# 04_4G.net
KiCad netlist of a schematic drawn in Altium Designer
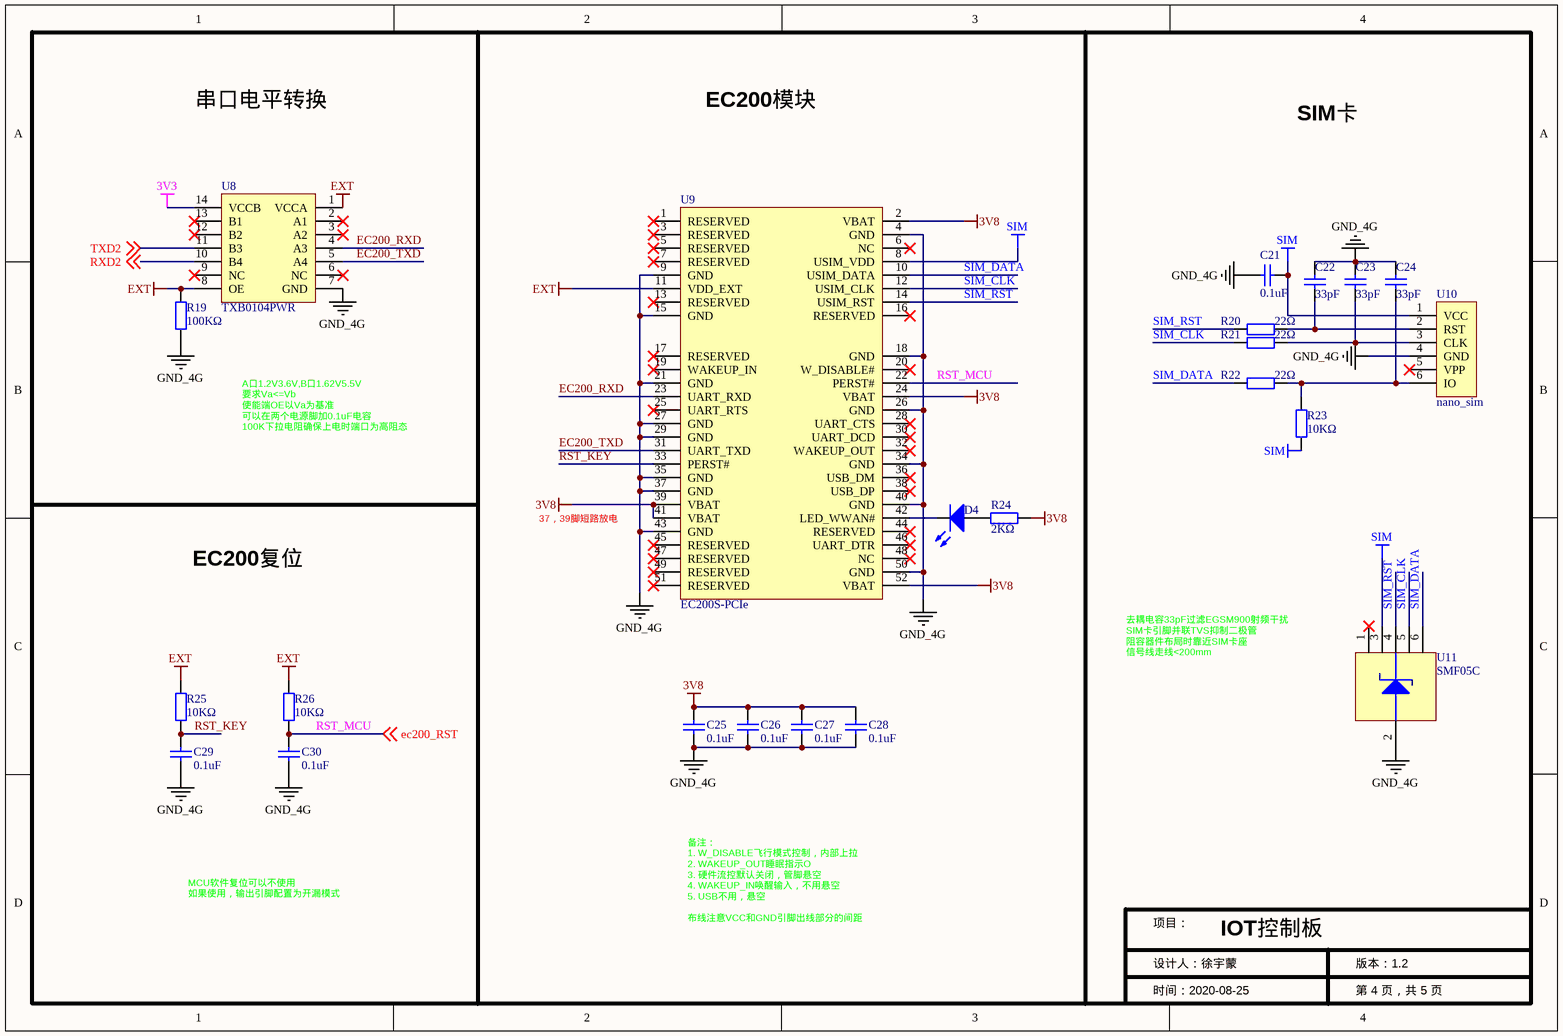
[diagram p0: 04_4G通信模块与外围电路.SchDoc]

(export (version "E")
  (design (tool "Eeschema 10.0.6"))
  (components
    (comp (ref "C21")
      (value "0.1uF")
      (footprint "CAP-0603")
      (description "无极性电容")
      (fields (field (name "Comment") "Cap") (field (name "PUBLISHER") "Altium Limited"))
      (libsource (lib "Arrowy_Racing") (part "Cap"))
    )
    (comp (ref "C22")
      (value "33pF")
      (footprint "CAP-0603")
      (description "无极性电容")
      (fields (field (name "Comment") "Cap") (field (name "PUBLISHER") "Altium Limited"))
      (libsource (lib "Arrowy_Racing") (part "Cap"))
    )
    (comp (ref "C23")
      (value "33pF")
      (footprint "CAP-0603")
      (description "无极性电容")
      (fields (field (name "Comment") "Cap") (field (name "PUBLISHER") "Altium Limited"))
      (libsource (lib "Arrowy_Racing") (part "Cap"))
    )
    (comp (ref "C24")
      (value "33pF")
      (footprint "CAP-0603")
      (description "无极性电容")
      (fields (field (name "Comment") "Cap") (field (name "PUBLISHER") "Altium Limited"))
      (libsource (lib "Arrowy_Racing") (part "Cap"))
    )
    (comp (ref "C25")
      (value "0.1uF")
      (footprint "CAP-0603")
      (description "无极性电容")
      (fields (field (name "Comment") "Cap") (field (name "PUBLISHER") "Altium Limited"))
      (libsource (lib "Arrowy_Racing") (part "Cap"))
    )
    (comp (ref "C26")
      (value "0.1uF")
      (footprint "CAP-0603")
      (description "无极性电容")
      (fields (field (name "Comment") "Cap") (field (name "PUBLISHER") "Altium Limited"))
      (libsource (lib "Arrowy_Racing") (part "Cap"))
    )
    (comp (ref "C27")
      (value "0.1uF")
      (footprint "CAP-0603")
      (description "无极性电容")
      (fields (field (name "Comment") "Cap") (field (name "PUBLISHER") "Altium Limited"))
      (libsource (lib "Arrowy_Racing") (part "Cap"))
    )
    (comp (ref "C28")
      (value "0.1uF")
      (footprint "CAP-0603")
      (description "无极性电容")
      (fields (field (name "Comment") "Cap") (field (name "PUBLISHER") "Altium Limited"))
      (libsource (lib "Arrowy_Racing") (part "Cap"))
    )
    (comp (ref "C29")
      (value "0.1uF")
      (footprint "CAP-0603")
      (description "无极性电容")
      (fields (field (name "Comment") "Cap") (field (name "PUBLISHER") "Altium Limited"))
      (libsource (lib "Arrowy_Racing") (part "Cap"))
    )
    (comp (ref "C30")
      (value "0.1uF")
      (footprint "CAP-0603")
      (description "无极性电容")
      (fields (field (name "Comment") "Cap") (field (name "PUBLISHER") "Altium Limited"))
      (libsource (lib "Arrowy_Racing") (part "Cap"))
    )
    (comp (ref "D4")
      (value "LED")
      (footprint "LED_0805")
      (description "发光二极管")
      (fields (field (name "PUBLISHER") "Altium Limited"))
      (libsource (lib "Arrowy_Racing") (part "LED"))
    )
    (comp (ref "R19")
      (value "100KΩ")
      (footprint "0603")
      (description "贴片电阻")
      (fields (field (name "Comment") "Res") (field (name "PUBLISHER") "Altium Limited"))
      (libsource (lib "") (part "Res_1"))
    )
    (comp (ref "R20")
      (value "22Ω")
      (footprint "0603")
      (description "贴片电阻")
      (fields (field (name "Comment") "Res") (field (name "PUBLISHER") "Altium Limited"))
      (libsource (lib "") (part "Res_1"))
    )
    (comp (ref "R21")
      (value "22Ω")
      (footprint "0603")
      (description "贴片电阻")
      (fields (field (name "Comment") "Res") (field (name "PUBLISHER") "Altium Limited"))
      (libsource (lib "") (part "Res_1"))
    )
    (comp (ref "R22")
      (value "22Ω")
      (footprint "0603")
      (description "贴片电阻")
      (fields (field (name "Comment") "Res") (field (name "PUBLISHER") "Altium Limited"))
      (libsource (lib "") (part "Res_1"))
    )
    (comp (ref "R23")
      (value "10KΩ")
      (footprint "0603")
      (description "贴片电阻")
      (fields (field (name "Comment") "Res") (field (name "PUBLISHER") "Altium Limited"))
      (libsource (lib "") (part "Res_3"))
    )
    (comp (ref "R24")
      (value "2KΩ")
      (footprint "0603")
      (description "贴片电阻")
      (fields (field (name "Comment") "Res") (field (name "PUBLISHER") "Altium Limited"))
      (libsource (lib "") (part "Res_2"))
    )
    (comp (ref "R25")
      (value "10KΩ")
      (footprint "0603")
      (description "贴片电阻")
      (fields (field (name "Comment") "Res") (field (name "PUBLISHER") "Altium Limited"))
      (libsource (lib "Arrowy_Racing") (part "Res"))
    )
    (comp (ref "R26")
      (value "10KΩ")
      (footprint "0603")
      (description "贴片电阻")
      (fields (field (name "Comment") "Res") (field (name "PUBLISHER") "Altium Limited"))
      (libsource (lib "") (part "Res_3"))
    )
    (comp (ref "U8")
      (value "TXB0104PWR")
      (footprint "TSSOP-14")
      (description "电平转换芯片")
      (libsource (lib "Arrowy_Racing") (part "TXB0104PWR"))
    )
    (comp (ref "U9")
      (value "EC200S-PCIe")
      (footprint "miniPCIe1")
      (libsource (lib "Arrowy_Racing") (part "EC200T-PCIe"))
    )
    (comp (ref "U10")
      (value "nano_sim")
      (footprint "Nano_SIM_6P")
      (libsource (lib "Arrowy_Racing") (part "nano_sim"))
    )
    (comp (ref "U11")
      (value "SMF05C")
      (footprint "SOT-363")
      (libsource (lib "Arrowy_Racing") (part "SMF05C"))
    )
  )
  (nets
    (net (code "1") (name "/EC200_RXD") (class "Default")
      (node (ref "U8") (pin "4") (pinfunction "A3_4") (pintype "passive"))
      (node (ref "U9") (pin "23") (pinfunction "UART_RXD_23") (pintype "passive"))
    )
    (net (code "2") (name "/EC200_TXD") (class "Default")
      (node (ref "U8") (pin "5") (pinfunction "A4_5") (pintype "passive"))
      (node (ref "U9") (pin "31") (pinfunction "UART_TXD_31") (pintype "passive"))
    )
    (net (code "3") (name "/RST_KEY") (class "Default")
      (node (ref "C29") (pin "2") (pinfunction "2_2") (pintype "passive"))
      (node (ref "R25") (pin "1") (pinfunction "1_1") (pintype "passive"))
      (node (ref "U9") (pin "33") (pinfunction "PERST#_33") (pintype "passive"))
    )
    (net (code "4") (name "/SIM_CLK") (class "Default")
      (node (ref "R21") (pin "1") (pinfunction "1_1") (pintype "passive"))
      (node (ref "U11") (pin "5") (pinfunction "gnd_5") (pintype "passive"))
      (node (ref "U9") (pin "12") (pinfunction "USIM_CLK_12") (pintype "passive"))
    )
    (net (code "5") (name "/SIM_DATA") (class "Default")
      (node (ref "R22") (pin "1") (pinfunction "1_1") (pintype "passive"))
      (node (ref "U11") (pin "6") (pinfunction "gnd_6") (pintype "passive"))
      (node (ref "U9") (pin "10") (pinfunction "USIM_DATA_10") (pintype "passive"))
    )
    (net (code "6") (name "/SIM_RST") (class "Default")
      (node (ref "R20") (pin "1") (pinfunction "1_1") (pintype "passive"))
      (node (ref "U11") (pin "4") (pinfunction "gnd_4") (pintype "passive"))
      (node (ref "U9") (pin "14") (pinfunction "USIM_RST_14") (pintype "passive"))
    )
    (net (code "7") (name "3V3") (class "Default")
      (node (ref "U8") (pin "14") (pinfunction "VCCB_14") (pintype "passive"))
    )
    (net (code "8") (name "3V8") (class "Default")
      (node (ref "C25") (pin "2") (pinfunction "2_2") (pintype "passive"))
      (node (ref "C26") (pin "2") (pinfunction "2_2") (pintype "passive"))
      (node (ref "C27") (pin "2") (pinfunction "2_2") (pintype "passive"))
      (node (ref "C28") (pin "2") (pinfunction "2_2") (pintype "passive"))
      (node (ref "R24") (pin "1") (pinfunction "1_1") (pintype "passive"))
      (node (ref "U9") (pin "2") (pinfunction "VBAT_2") (pintype "passive"))
      (node (ref "U9") (pin "24") (pinfunction "VBAT_24") (pintype "passive"))
      (node (ref "U9") (pin "39") (pinfunction "VBAT_39") (pintype "passive"))
      (node (ref "U9") (pin "41") (pinfunction "VBAT_41") (pintype "passive"))
      (node (ref "U9") (pin "52") (pinfunction "VBAT_52") (pintype "passive"))
    )
    (net (code "9") (name "EXT") (class "Default")
      (node (ref "R19") (pin "2") (pinfunction "2_2") (pintype "passive"))
      (node (ref "R25") (pin "2") (pinfunction "2_2") (pintype "passive"))
      (node (ref "R26") (pin "1") (pinfunction "1_1") (pintype "passive"))
      (node (ref "U8") (pin "1") (pinfunction "VCCA_1") (pintype "passive"))
      (node (ref "U8") (pin "8") (pinfunction "OE_8") (pintype "passive"))
      (node (ref "U9") (pin "11") (pinfunction "VDD_EXT_11") (pintype "passive"))
    )
    (net (code "10") (name "GND_4G") (class "Default")
      (node (ref "C21") (pin "2") (pinfunction "2_2") (pintype "passive"))
      (node (ref "C22") (pin "1") (pinfunction "1_1") (pintype "passive"))
      (node (ref "C23") (pin "1") (pinfunction "1_1") (pintype "passive"))
      (node (ref "C24") (pin "2") (pinfunction "2_2") (pintype "passive"))
      (node (ref "C25") (pin "1") (pinfunction "1_1") (pintype "passive"))
      (node (ref "C26") (pin "1") (pinfunction "1_1") (pintype "passive"))
      (node (ref "C27") (pin "1") (pinfunction "1_1") (pintype "passive"))
      (node (ref "C28") (pin "1") (pinfunction "1_1") (pintype "passive"))
      (node (ref "C29") (pin "1") (pinfunction "1_1") (pintype "passive"))
      (node (ref "C30") (pin "2") (pinfunction "2_2") (pintype "passive"))
      (node (ref "R19") (pin "1") (pinfunction "1_1") (pintype "passive"))
      (node (ref "U10") (pin "4") (pinfunction "GND_4") (pintype "passive"))
      (node (ref "U11") (pin "2") (pinfunction "gnd_2") (pintype "passive"))
      (node (ref "U8") (pin "7") (pinfunction "GND_7") (pintype "passive"))
      (node (ref "U9") (pin "15") (pinfunction "GND_15") (pintype "passive"))
      (node (ref "U9") (pin "18") (pinfunction "GND_18") (pintype "passive"))
      (node (ref "U9") (pin "21") (pinfunction "GND_21") (pintype "passive"))
      (node (ref "U9") (pin "26") (pinfunction "GND_26") (pintype "passive"))
      (node (ref "U9") (pin "27") (pinfunction "GND_27") (pintype "passive"))
      (node (ref "U9") (pin "29") (pinfunction "GND_29") (pintype "passive"))
      (node (ref "U9") (pin "34") (pinfunction "GND_34") (pintype "passive"))
      (node (ref "U9") (pin "35") (pinfunction "GND_35") (pintype "passive"))
      (node (ref "U9") (pin "37") (pinfunction "GND_37") (pintype "passive"))
      (node (ref "U9") (pin "4") (pinfunction "GND_4") (pintype "passive"))
      (node (ref "U9") (pin "40") (pinfunction "GND_40") (pintype "passive"))
      (node (ref "U9") (pin "43") (pinfunction "GND_43") (pintype "passive"))
      (node (ref "U9") (pin "50") (pinfunction "GND_50") (pintype "passive"))
      (node (ref "U9") (pin "9") (pinfunction "GND_9") (pintype "passive"))
    )
    (net (code "11") (name "Net-(D4-A)") (class "Default")
      (node (ref "D4") (pin "1") (pinfunction "A_1") (pintype "passive"))
      (node (ref "R24") (pin "2") (pinfunction "2_2") (pintype "passive"))
    )
    (net (code "12") (name "Net-(D4-K)") (class "Default")
      (node (ref "D4") (pin "2") (pinfunction "K_2") (pintype "passive"))
      (node (ref "U9") (pin "42") (pinfunction "LED_WWAN#_42") (pintype "passive"))
    )
    (net (code "13") (name "Net-(U10-CLK)") (class "Default")
      (node (ref "C23") (pin "2") (pinfunction "2_2") (pintype "passive"))
      (node (ref "R21") (pin "2") (pinfunction "2_2") (pintype "passive"))
      (node (ref "U10") (pin "3") (pinfunction "CLK_3") (pintype "passive"))
    )
    (net (code "14") (name "Net-(U10-IO)") (class "Default")
      (node (ref "C24") (pin "1") (pinfunction "1_1") (pintype "passive"))
      (node (ref "R22") (pin "2") (pinfunction "2_2") (pintype "passive"))
      (node (ref "R23") (pin "1") (pinfunction "1_1") (pintype "passive"))
      (node (ref "U10") (pin "6") (pinfunction "IO_6") (pintype "passive"))
    )
    (net (code "15") (name "Net-(U10-RST)") (class "Default")
      (node (ref "C22") (pin "2") (pinfunction "2_2") (pintype "passive"))
      (node (ref "R20") (pin "2") (pinfunction "2_2") (pintype "passive"))
      (node (ref "U10") (pin "2") (pinfunction "RST_2") (pintype "passive"))
    )
    (net (code "16") (name "RXD2") (class "Default")
      (node (ref "U8") (pin "10") (pinfunction "B4_10") (pintype "passive"))
    )
    (net (code "17") (name "SIM") (class "Default")
      (node (ref "C21") (pin "1") (pinfunction "1_1") (pintype "passive"))
      (node (ref "R23") (pin "2") (pinfunction "2_2") (pintype "passive"))
      (node (ref "U10") (pin "1") (pinfunction "VCC_1") (pintype "passive"))
      (node (ref "U11") (pin "3") (pinfunction "gnd_3") (pintype "passive"))
      (node (ref "U9") (pin "8") (pinfunction "USIM_VDD_8") (pintype "passive"))
    )
    (net (code "18") (name "TXD2") (class "Default")
      (node (ref "U8") (pin "11") (pinfunction "B3_11") (pintype "passive"))
    )
    (net (code "19") (name "ec200_RST") (class "Default")
      (node (ref "C30") (pin "1") (pinfunction "1_1") (pintype "passive"))
      (node (ref "R26") (pin "2") (pinfunction "2_2") (pintype "passive"))
      (node (ref "U9") (pin "22") (pinfunction "PERST#_22") (pintype "passive"))
    )
    (net (code "20") (name "unconnected-(U8-A1-Pad2)") (class "Default")
      (node (ref "U8") (pin "2") (pinfunction "A1_2") (pintype "passive+no_connect"))
    )
    (net (code "21") (name "unconnected-(U8-A2-Pad3)") (class "Default")
      (node (ref "U8") (pin "3") (pinfunction "A2_3") (pintype "passive+no_connect"))
    )
    (net (code "22") (name "unconnected-(U8-B1-Pad13)") (class "Default")
      (node (ref "U8") (pin "13") (pinfunction "B1_13") (pintype "passive+no_connect"))
    )
    (net (code "23") (name "unconnected-(U8-B2-Pad12)") (class "Default")
      (node (ref "U8") (pin "12") (pinfunction "B2_12") (pintype "passive+no_connect"))
    )
    (net (code "24") (name "unconnected-(U8-NC-Pad6)") (class "Default")
      (node (ref "U8") (pin "6") (pinfunction "NC_6") (pintype "passive+no_connect"))
    )
    (net (code "25") (name "unconnected-(U8-NC-Pad9)") (class "Default")
      (node (ref "U8") (pin "9") (pinfunction "NC_9") (pintype "passive+no_connect"))
    )
    (net (code "26") (name "unconnected-(U9-NC-Pad6)") (class "Default")
      (node (ref "U9") (pin "6") (pinfunction "NC_6") (pintype "passive+no_connect"))
    )
    (net (code "27") (name "unconnected-(U9-NC-Pad48)") (class "Default")
      (node (ref "U9") (pin "48") (pinfunction "NC_48") (pintype "passive+no_connect"))
    )
    (net (code "28") (name "unconnected-(U9-RESERVED-Pad1)") (class "Default")
      (node (ref "U9") (pin "1") (pinfunction "RESERVED_1") (pintype "passive+no_connect"))
    )
    (net (code "29") (name "unconnected-(U9-RESERVED-Pad3)") (class "Default")
      (node (ref "U9") (pin "3") (pinfunction "RESERVED_3") (pintype "passive+no_connect"))
    )
    (net (code "30") (name "unconnected-(U9-RESERVED-Pad5)") (class "Default")
      (node (ref "U9") (pin "5") (pinfunction "RESERVED_5") (pintype "passive+no_connect"))
    )
    (net (code "31") (name "unconnected-(U9-RESERVED-Pad7)") (class "Default")
      (node (ref "U9") (pin "7") (pinfunction "RESERVED_7") (pintype "passive+no_connect"))
    )
    (net (code "32") (name "unconnected-(U9-RESERVED-Pad13)") (class "Default")
      (node (ref "U9") (pin "13") (pinfunction "RESERVED_13") (pintype "passive+no_connect"))
    )
    (net (code "33") (name "unconnected-(U9-RESERVED-Pad16)") (class "Default")
      (node (ref "U9") (pin "16") (pinfunction "RESERVED_16") (pintype "passive+no_connect"))
    )
    (net (code "34") (name "unconnected-(U9-RESERVED-Pad17)") (class "Default")
      (node (ref "U9") (pin "17") (pinfunction "RESERVED_17") (pintype "passive+no_connect"))
    )
    (net (code "35") (name "unconnected-(U9-RESERVED-Pad44)") (class "Default")
      (node (ref "U9") (pin "44") (pinfunction "RESERVED_44") (pintype "passive+no_connect"))
    )
    (net (code "36") (name "unconnected-(U9-RESERVED-Pad45)") (class "Default")
      (node (ref "U9") (pin "45") (pinfunction "RESERVED_45") (pintype "passive+no_connect"))
    )
    (net (code "37") (name "unconnected-(U9-RESERVED-Pad47)") (class "Default")
      (node (ref "U9") (pin "47") (pinfunction "RESERVED_47") (pintype "passive+no_connect"))
    )
    (net (code "38") (name "unconnected-(U9-RESERVED-Pad49)") (class "Default")
      (node (ref "U9") (pin "49") (pinfunction "RESERVED_49") (pintype "passive+no_connect"))
    )
    (net (code "39") (name "unconnected-(U9-RESERVED-Pad51)") (class "Default")
      (node (ref "U9") (pin "51") (pinfunction "RESERVED_51") (pintype "passive+no_connect"))
    )
    (net (code "40") (name "unconnected-(U9-UART_CTS-Pad28)") (class "Default")
      (node (ref "U9") (pin "28") (pinfunction "UART_CTS_28") (pintype "passive+no_connect"))
    )
    (net (code "41") (name "unconnected-(U9-UART_DCD-Pad30)") (class "Default")
      (node (ref "U9") (pin "30") (pinfunction "UART_DCD_30") (pintype "passive+no_connect"))
    )
    (net (code "42") (name "unconnected-(U9-UART_DTR-Pad46)") (class "Default")
      (node (ref "U9") (pin "46") (pinfunction "UART_DTR_46") (pintype "passive+no_connect"))
    )
    (net (code "43") (name "unconnected-(U9-UART_RTS-Pad25)") (class "Default")
      (node (ref "U9") (pin "25") (pinfunction "UART_RTS_25") (pintype "passive+no_connect"))
    )
    (net (code "44") (name "unconnected-(U9-USB_DM-Pad36)") (class "Default")
      (node (ref "U9") (pin "36") (pinfunction "USB_DM_36") (pintype "passive+no_connect"))
    )
    (net (code "45") (name "unconnected-(U9-USB_DP-Pad38)") (class "Default")
      (node (ref "U9") (pin "38") (pinfunction "USB_DP_38") (pintype "passive+no_connect"))
    )
    (net (code "46") (name "unconnected-(U9-WAKEUP_IN-Pad19)") (class "Default")
      (node (ref "U9") (pin "19") (pinfunction "WAKEUP_IN_19") (pintype "passive+no_connect"))
    )
    (net (code "47") (name "unconnected-(U9-WAKEUP_OUT-Pad32)") (class "Default")
      (node (ref "U9") (pin "32") (pinfunction "WAKEUP_OUT_32") (pintype "passive+no_connect"))
    )
    (net (code "48") (name "unconnected-(U9-W_DISABLE#-Pad20)") (class "Default")
      (node (ref "U9") (pin "20") (pinfunction "W_DISABLE#_20") (pintype "passive+no_connect"))
    )
    (net (code "49") (name "unconnected-(U10-VPP-Pad5)") (class "Default")
      (node (ref "U10") (pin "5") (pinfunction "VPP_5") (pintype "passive+no_connect"))
    )
    (net (code "50") (name "unconnected-(U11-gnd-Pad1)") (class "Default")
      (node (ref "U11") (pin "1") (pinfunction "gnd_1") (pintype "passive+no_connect"))
    )
  )
)
